# design.net
KiCad netlist of a schematic drawn in Altium Designer
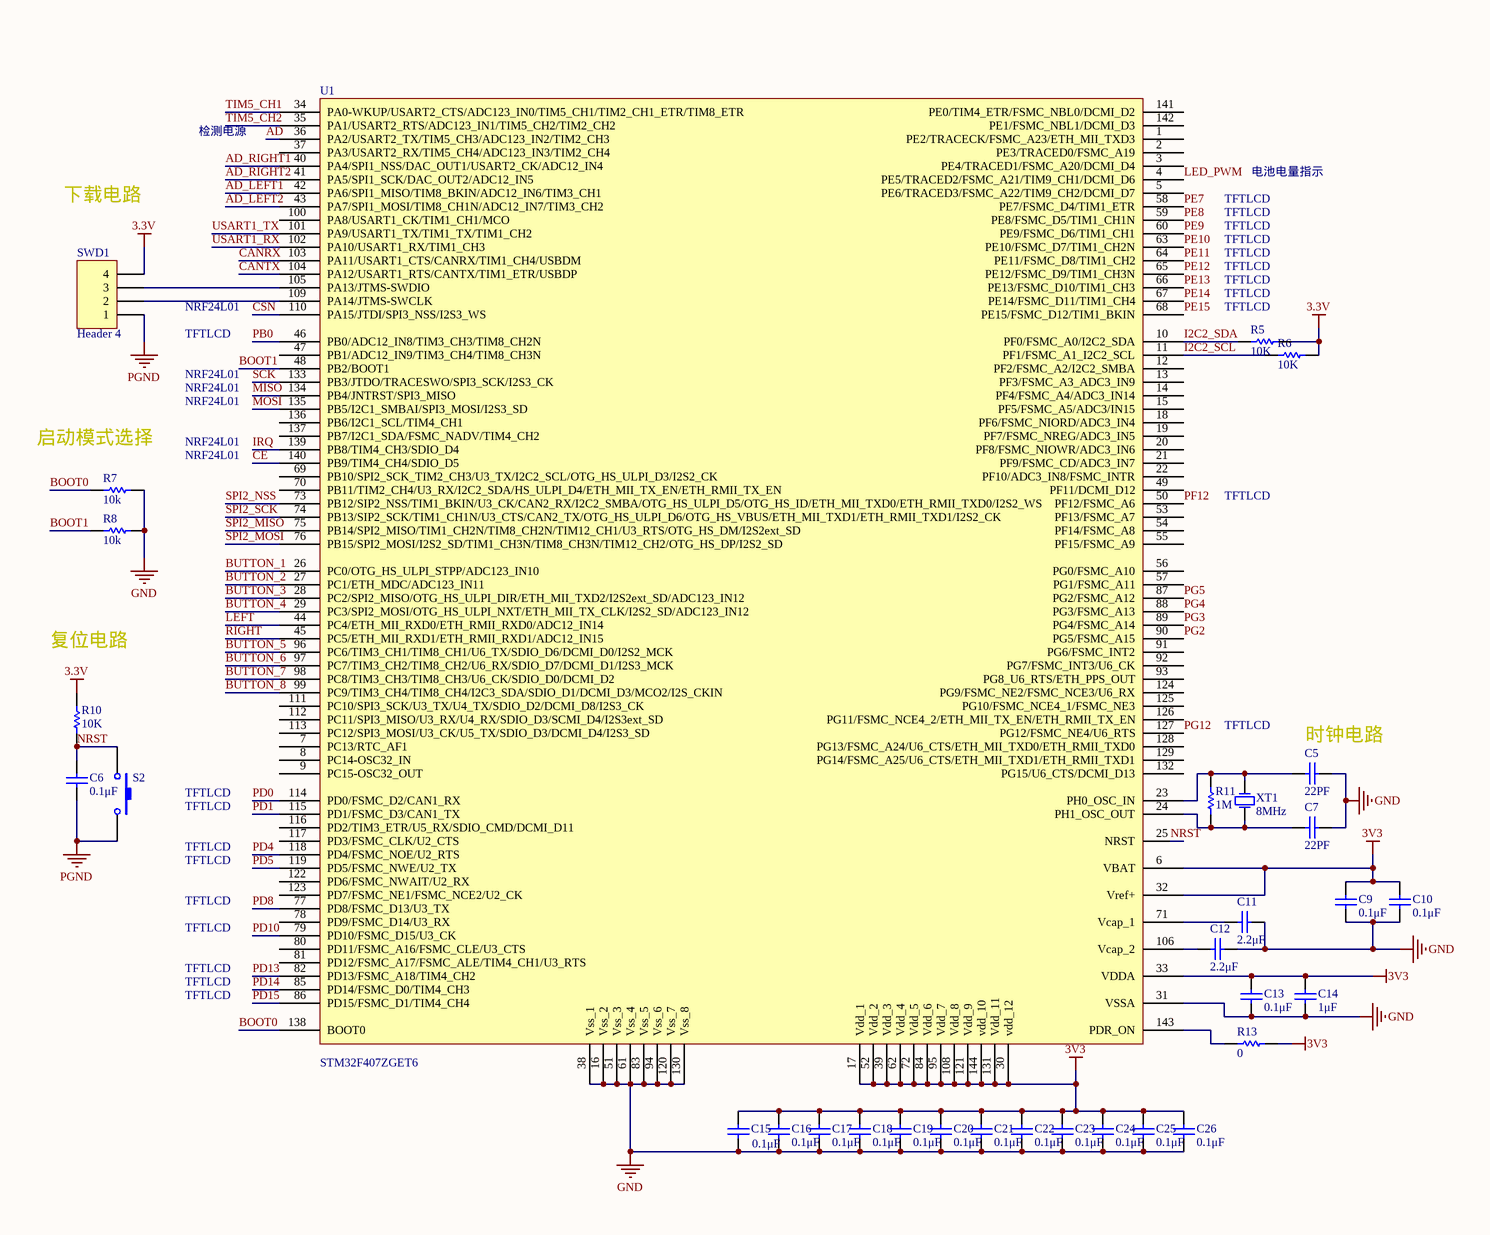
[diagram p0: 手柄.SchDoc, left]
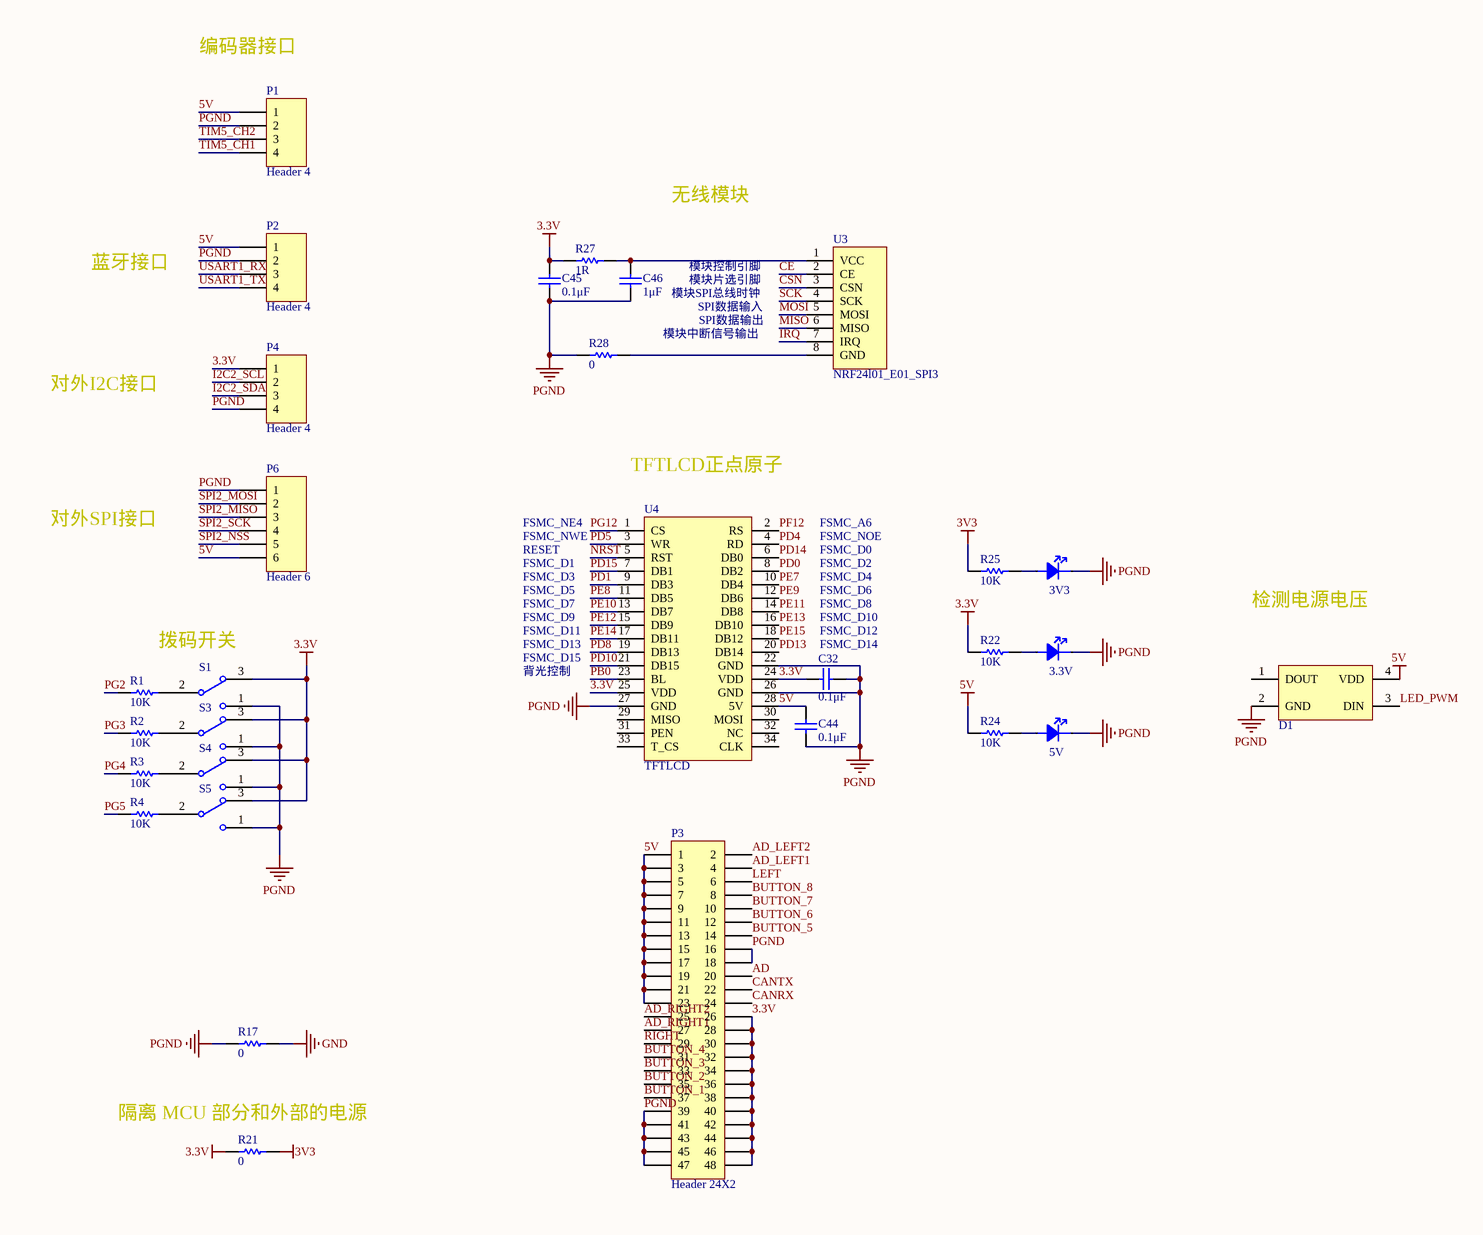
[diagram p1: 手柄.SchDoc, right]

(export (version "E")
  (design (tool "Eeschema 10.0.6"))
  (components
    (comp (ref "3.3V")
      (value "lED")
      (footprint "0805D")
      (description "LED")
      (libsource (lib "K60-mainboard-v3.1") (part "00-D-LED"))
    )
    (comp (ref "3V3")
      (value "lED")
      (footprint "0805D")
      (description "LED")
      (libsource (lib "K60-mainboard-v3.1") (part "00-D-LED"))
    )
    (comp (ref "5V")
      (value "lED")
      (footprint "0805D")
      (description "LED")
      (libsource (lib "K60-mainboard-v3.1") (part "00-D-LED"))
    )
    (comp (ref "C5")
      (value "22PF")
      (footprint "CAP-MLCC-0603")
      (description "无极性电容")
      (fields (field (name "PUBLISHER") "Altium Limited"))
      (libsource (lib "Libraries_2014_0618") (part "CAP"))
    )
    (comp (ref "C6")
      (value "0.1μF")
      (footprint "CAP-MLCC-0603")
      (description "无极性电容")
      (fields (field (name "PUBLISHER") "Altium Limited"))
      (libsource (lib "Libraries_2014_0618") (part "CAP"))
    )
    (comp (ref "C7")
      (value "22PF")
      (footprint "CAP-MLCC-0603")
      (description "无极性电容")
      (fields (field (name "PUBLISHER") "Altium Limited"))
      (libsource (lib "Libraries_2014_0618") (part "CAP"))
    )
    (comp (ref "C9")
      (value "0.1μF")
      (footprint "CAP-MLCC-0603")
      (description "无极性电容")
      (fields (field (name "PUBLISHER") "Altium Limited"))
      (libsource (lib "Libraries_2014_0618") (part "CAP"))
    )
    (comp (ref "C10")
      (value "0.1μF")
      (footprint "CAP-MLCC-0603")
      (description "无极性电容")
      (fields (field (name "PUBLISHER") "Altium Limited"))
      (libsource (lib "Libraries_2014_0618") (part "CAP"))
    )
    (comp (ref "C11")
      (value "2.2μF")
      (footprint "CAP-MLCC-0603")
      (description "无极性电容")
      (fields (field (name "PUBLISHER") "Altium Limited"))
      (libsource (lib "Libraries_2014_0618") (part "CAP"))
    )
    (comp (ref "C12")
      (value "2.2μF")
      (footprint "CAP-MLCC-0603")
      (description "无极性电容")
      (fields (field (name "PUBLISHER") "Altium Limited"))
      (libsource (lib "Libraries_2014_0618") (part "CAP"))
    )
    (comp (ref "C13")
      (value "0.1μF")
      (footprint "CAP-MLCC-0603")
      (description "无极性电容")
      (fields (field (name "PUBLISHER") "Altium Limited"))
      (libsource (lib "Libraries_2014_0618") (part "CAP"))
    )
    (comp (ref "C14")
      (value "1μF")
      (footprint "CAP-MLCC-0603")
      (description "无极性电容")
      (fields (field (name "PUBLISHER") "Altium Limited"))
      (libsource (lib "Libraries_2014_0618") (part "CAP"))
    )
    (comp (ref "C15")
      (value "0.1μF")
      (footprint "CAP-MLCC-0603")
      (description "无极性电容")
      (fields (field (name "PUBLISHER") "Altium Limited"))
      (libsource (lib "Libraries_2014_0618") (part "CAP"))
    )
    (comp (ref "C16")
      (value "0.1μF")
      (footprint "CAP-MLCC-0603")
      (description "无极性电容")
      (fields (field (name "PUBLISHER") "Altium Limited"))
      (libsource (lib "Libraries_2014_0618") (part "CAP"))
    )
    (comp (ref "C17")
      (value "0.1μF")
      (footprint "CAP-MLCC-0603")
      (description "无极性电容")
      (fields (field (name "PUBLISHER") "Altium Limited"))
      (libsource (lib "Libraries_2014_0618") (part "CAP"))
    )
    (comp (ref "C18")
      (value "0.1μF")
      (footprint "CAP-MLCC-0603")
      (description "无极性电容")
      (fields (field (name "PUBLISHER") "Altium Limited"))
      (libsource (lib "Libraries_2014_0618") (part "CAP"))
    )
    (comp (ref "C19")
      (value "0.1μF")
      (footprint "CAP-MLCC-0603")
      (description "无极性电容")
      (fields (field (name "PUBLISHER") "Altium Limited"))
      (libsource (lib "Libraries_2014_0618") (part "CAP"))
    )
    (comp (ref "C20")
      (value "0.1μF")
      (footprint "CAP-MLCC-0603")
      (description "无极性电容")
      (fields (field (name "PUBLISHER") "Altium Limited"))
      (libsource (lib "Libraries_2014_0618") (part "CAP"))
    )
    (comp (ref "C21")
      (value "0.1μF")
      (footprint "CAP-MLCC-0603")
      (description "无极性电容")
      (fields (field (name "PUBLISHER") "Altium Limited"))
      (libsource (lib "Libraries_2014_0618") (part "CAP"))
    )
    (comp (ref "C22")
      (value "0.1μF")
      (footprint "CAP-MLCC-0603")
      (description "无极性电容")
      (fields (field (name "PUBLISHER") "Altium Limited"))
      (libsource (lib "Libraries_2014_0618") (part "CAP"))
    )
    (comp (ref "C23")
      (value "0.1μF")
      (footprint "CAP-MLCC-0603")
      (description "无极性电容")
      (fields (field (name "PUBLISHER") "Altium Limited"))
      (libsource (lib "Libraries_2014_0618") (part "CAP"))
    )
    (comp (ref "C24")
      (value "0.1μF")
      (footprint "CAP-MLCC-0603")
      (description "无极性电容")
      (fields (field (name "PUBLISHER") "Altium Limited"))
      (libsource (lib "Libraries_2014_0618") (part "CAP"))
    )
    (comp (ref "C25")
      (value "0.1μF")
      (footprint "CAP-MLCC-0603")
      (description "无极性电容")
      (fields (field (name "PUBLISHER") "Altium Limited"))
      (libsource (lib "Libraries_2014_0618") (part "CAP"))
    )
    (comp (ref "C26")
      (value "0.1μF")
      (footprint "CAP-MLCC-0603")
      (description "无极性电容")
      (fields (field (name "PUBLISHER") "Altium Limited"))
      (libsource (lib "Libraries_2014_0618") (part "CAP"))
    )
    (comp (ref "C32")
      (value "0.1μF")
      (footprint "CAP-MLCC-0603")
      (description "无极性电容")
      (fields (field (name "PUBLISHER") "Altium Limited"))
      (libsource (lib "Libraries_2014_0618") (part "CAP"))
    )
    (comp (ref "C44")
      (value "0.1μF")
      (footprint "CAP-MLCC-0603")
      (description "无极性电容")
      (fields (field (name "PUBLISHER") "Altium Limited"))
      (libsource (lib "Libraries_2014_0618") (part "CAP"))
    )
    (comp (ref "C45")
      (value "0.1μF")
      (footprint "CAP-MLCC-0603")
      (description "无极性电容")
      (fields (field (name "PUBLISHER") "Altium Limited"))
      (libsource (lib "Libraries_2014_0618") (part "CAP"))
    )
    (comp (ref "C46")
      (value "1μF")
      (footprint "CAP-MLCC-0603")
      (description "无极性电容")
      (fields (field (name "PUBLISHER") "Altium Limited"))
      (libsource (lib "Libraries_2014_0618") (part "CAP"))
    )
    (comp (ref "D1")
      (value "LED_3535_SK6812")
      (footprint "PCB_ActiveLED:LED_3535_4P")
      (description "LED")
      (libsource (lib "SCH_Active") (part "LED_3535_SK6812"))
    )
    (comp (ref "P1")
      (value "Header 4")
      (footprint "HDR1X4")
      (description "Header, 4-Pin")
      (fields (field (name "PUBLISHER") "Altium Limited"))
      (libsource (lib "") (part "Header 4_1"))
    )
    (comp (ref "P2")
      (value "Header 4")
      (footprint "HDR1X4")
      (description "Header, 4-Pin")
      (fields (field (name "PUBLISHER") "Altium Limited"))
      (libsource (lib "") (part "Header 4_1"))
    )
    (comp (ref "P3")
      (value "Header 24X2")
      (footprint "手柄下板")
      (description "Header, 24-Pin, Dual row")
      (fields (field (name "PUBLISHER") "Altium Limited"))
      (libsource (lib "Libraries_2014_0618") (part "Header 24X2"))
    )
    (comp (ref "P4")
      (value "Header 4")
      (footprint "HDR1X4")
      (description "Header, 4-Pin")
      (fields (field (name "PUBLISHER") "Altium Limited"))
      (libsource (lib "Libraries_2014_0618") (part "Header 4"))
    )
    (comp (ref "P6")
      (value "Header 6")
      (footprint "Header 6")
      (description "Header, 6-Pin")
      (fields (field (name "PUBLISHER") "Altium Limited"))
      (libsource (lib "Libraries_2014_0618") (part "Header 6"))
    )
    (comp (ref "R1")
      (value "10K")
      (footprint "RES-0603")
      (description "Resistor")
      (fields (field (name "Comment") "Res1") (field (name "PUBLISHER") "Altium Limited"))
      (libsource (lib "K60-mainboard-v3.1") (part "Res1"))
    )
    (comp (ref "R2")
      (value "10K")
      (footprint "RES-0603")
      (description "Resistor")
      (fields (field (name "Comment") "Res1") (field (name "PUBLISHER") "Altium Limited"))
      (libsource (lib "K60-mainboard-v3.1") (part "Res1"))
    )
    (comp (ref "R3")
      (value "10K")
      (footprint "RES-0603")
      (description "Resistor")
      (fields (field (name "Comment") "Res1") (field (name "PUBLISHER") "Altium Limited"))
      (libsource (lib "K60-mainboard-v3.1") (part "Res1"))
    )
    (comp (ref "R4")
      (value "10K")
      (footprint "RES-0603")
      (description "Resistor")
      (fields (field (name "Comment") "Res1") (field (name "PUBLISHER") "Altium Limited"))
      (libsource (lib "K60-mainboard-v3.1") (part "Res1"))
    )
    (comp (ref "R5")
      (value "10K")
      (footprint "RES-0603")
      (description "Resistor")
      (fields (field (name "Comment") "Res1") (field (name "PUBLISHER") "Altium Limited"))
      (libsource (lib "K60-mainboard-v3.1") (part "Res1"))
    )
    (comp (ref "R6")
      (value "10K")
      (footprint "RES-0603")
      (description "Resistor")
      (fields (field (name "Comment") "Res1") (field (name "PUBLISHER") "Altium Limited"))
      (libsource (lib "K60-mainboard-v3.1") (part "Res1"))
    )
    (comp (ref "R7")
      (value "10k")
      (footprint "RES-0603")
      (description "Resistor")
      (fields (field (name "Comment") "Res1") (field (name "PUBLISHER") "Altium Limited"))
      (libsource (lib "K60-mainboard-v3.1") (part "Res1"))
    )
    (comp (ref "R8")
      (value "10k")
      (footprint "RES-0603")
      (description "Resistor")
      (fields (field (name "Comment") "Res1") (field (name "PUBLISHER") "Altium Limited"))
      (libsource (lib "K60-mainboard-v3.1") (part "Res1"))
    )
    (comp (ref "R10")
      (value "10K")
      (footprint "RES-0603")
      (description "Resistor")
      (fields (field (name "Comment") "Res1") (field (name "PUBLISHER") "Altium Limited"))
      (libsource (lib "K60-mainboard-v3.1") (part "Res1"))
    )
    (comp (ref "R11")
      (value "1M")
      (footprint "RES-0603")
      (description "Resistor")
      (fields (field (name "Comment") "Res1") (field (name "PUBLISHER") "Altium Limited"))
      (libsource (lib "K60-mainboard-v3.1") (part "Res1"))
    )
    (comp (ref "R13")
      (value "0")
      (footprint "RES-0603")
      (description "Resistor")
      (fields (field (name "Comment") "Res1") (field (name "PUBLISHER") "Altium Limited"))
      (libsource (lib "K60-mainboard-v3.1") (part "Res1"))
    )
    (comp (ref "R17")
      (value "0")
      (footprint "RES-0603")
      (description "Resistor")
      (fields (field (name "Comment") "Res1") (field (name "PUBLISHER") "Altium Limited"))
      (libsource (lib "K60-mainboard-v3.1") (part "Res1"))
    )
    (comp (ref "R21")
      (value "0")
      (footprint "RES-0603")
      (description "Resistor")
      (fields (field (name "Comment") "Res1") (field (name "PUBLISHER") "Altium Limited"))
      (libsource (lib "K60-mainboard-v3.1") (part "Res1"))
    )
    (comp (ref "R22")
      (value "10K")
      (footprint "RES-0603")
      (description "Resistor")
      (fields (field (name "Comment") "Res1") (field (name "PUBLISHER") "Altium Limited"))
      (libsource (lib "K60-mainboard-v3.1") (part "Res1"))
    )
    (comp (ref "R24")
      (value "10K")
      (footprint "RES-0603")
      (description "Resistor")
      (fields (field (name "Comment") "Res1") (field (name "PUBLISHER") "Altium Limited"))
      (libsource (lib "K60-mainboard-v3.1") (part "Res1"))
    )
    (comp (ref "R25")
      (value "10K")
      (footprint "RES-0603")
      (description "Resistor")
      (fields (field (name "Comment") "Res1") (field (name "PUBLISHER") "Altium Limited"))
      (libsource (lib "K60-mainboard-v3.1") (part "Res1"))
    )
    (comp (ref "R27")
      (value "1R")
      (footprint "RES-0603")
      (description "Resistor")
      (fields (field (name "Comment") "Res1") (field (name "PUBLISHER") "Altium Limited"))
      (libsource (lib "K60-mainboard-v3.1") (part "Res1"))
    )
    (comp (ref "R28")
      (value "0")
      (footprint "RES-0603")
      (description "Resistor")
      (fields (field (name "Comment") "Res1") (field (name "PUBLISHER") "Altium Limited"))
      (libsource (lib "K60-mainboard-v3.1") (part "Res1"))
    )
    (comp (ref "S1")
      (value "SW-SPDT")
      (footprint "拨码开关")
      (description "单刀双掷开关")
      (fields (field (name "PUBLISHER") "Altium Limited"))
      (libsource (lib "Libraries_2014_0618") (part "SW-SPDT"))
    )
    (comp (ref "S2")
      (value "SW-PB")
      (footprint "KEY")
      (description "按钮")
      (fields (field (name "PUBLISHER") "Altium Limited"))
      (libsource (lib "Libraries_2014_0618") (part "SW-PB"))
    )
    (comp (ref "S3")
      (value "SW-SPDT")
      (footprint "拨码开关")
      (description "单刀双掷开关")
      (fields (field (name "PUBLISHER") "Altium Limited"))
      (libsource (lib "Libraries_2014_0618") (part "SW-SPDT"))
    )
    (comp (ref "S4")
      (value "SW-SPDT")
      (footprint "拨码开关")
      (description "单刀双掷开关")
      (fields (field (name "PUBLISHER") "Altium Limited"))
      (libsource (lib "Libraries_2014_0618") (part "SW-SPDT"))
    )
    (comp (ref "S5")
      (value "SW-SPDT")
      (footprint "拨码开关")
      (description "单刀双掷开关")
      (fields (field (name "PUBLISHER") "Altium Limited"))
      (libsource (lib "Libraries_2014_0618") (part "SW-SPDT"))
    )
    (comp (ref "SWD1")
      (value "Header 4")
      (footprint "HDR1X4")
      (description "Header, 4-Pin")
      (fields (field (name "PUBLISHER") "Altium Limited"))
      (libsource (lib "K60-mainboard-v3.1") (part "Header 4"))
    )
    (comp (ref "U1")
      (value "STM32F407ZGET6")
      (footprint "LQFP144-L")
      (libsource (lib "STM32F407VGT6") (part "Component_1"))
    )
    (comp (ref "U3")
      (value "NRF24l01_E01_SPI3")
      (footprint "E01-ML01SP2")
      (libsource (lib "SCH_Module") (part "NRF24l01_E01_SPI2"))
    )
    (comp (ref "U4") (value "TFTLCD") (footprint "TFTLCD") (libsource (lib "sensor") (part "TFTLCD")))
    (comp (ref "XT1")
      (value "8MHz")
      (footprint "PCB_Oscillator:XT_5032_2")
      (description "Crystal Oscillator")
      (fields (field (name "Comment") "XTAL_5032_2P"))
      (libsource (lib "SCH_Oscillator") (part "XTAL_5032_2P"))
    )
  )
  (nets
    (net (code "1") (name "/AD") (class "Default")
      (node (ref "P3") (pin "20") (pinfunction "20_20") (pintype "passive"))
      (node (ref "U1") (pin "36") (pinfunction "PA2/USART2_TX/TIM5_CH3/ADC123_IN2/TIM2_CH3_36") (pintype "passive"))
    )
    (net (code "2") (name "/AD_LEFT1") (class "Default")
      (node (ref "P3") (pin "4") (pinfunction "4_4") (pintype "passive"))
      (node (ref "U1") (pin "42") (pinfunction "PA6/SPI1_MISO/TIM8_BKIN/ADC12_IN6/TIM3_CH1_42") (pintype "passive"))
    )
    (net (code "3") (name "/AD_LEFT2") (class "Default")
      (node (ref "P3") (pin "2") (pinfunction "2_2") (pintype "passive"))
      (node (ref "U1") (pin "43") (pinfunction "PA7/SPI1_MOSI/TIM8_CH1N/ADC12_IN7/TIM3_CH2_43") (pintype "passive"))
    )
    (net (code "4") (name "/AD_RIGHT1") (class "Default")
      (node (ref "P3") (pin "27") (pinfunction "27_27") (pintype "passive"))
      (node (ref "U1") (pin "40") (pinfunction "PA4/SPI1_NSS/DAC_OUT1/USART2_CK/ADC12_IN4_40") (pintype "passive"))
    )
    (net (code "5") (name "/AD_RIGHT2") (class "Default")
      (node (ref "P3") (pin "25") (pinfunction "25_25") (pintype "passive"))
      (node (ref "U1") (pin "41") (pinfunction "PA5/SPI1_SCK/DAC_OUT2/ADC12_IN5_41") (pintype "passive"))
    )
    (net (code "6") (name "/BOOT0") (class "Default")
      (node (ref "R7") (pin "1") (pinfunction "1_1") (pintype "passive"))
      (node (ref "U1") (pin "138") (pinfunction "BOOT0_138") (pintype "passive"))
    )
    (net (code "7") (name "/BOOT1") (class "Default")
      (node (ref "R8") (pin "1") (pinfunction "1_1") (pintype "passive"))
      (node (ref "U1") (pin "48") (pinfunction "PB2/BOOT1_48") (pintype "passive"))
    )
    (net (code "8") (name "/BUTTON_1") (class "Default")
      (node (ref "P3") (pin "37") (pinfunction "37_37") (pintype "passive"))
      (node (ref "U1") (pin "26") (pinfunction "PC0/OTG_HS_ULPI_STPP/ADC123_IN10_26") (pintype "passive"))
    )
    (net (code "9") (name "/BUTTON_2") (class "Default")
      (node (ref "P3") (pin "35") (pinfunction "35_35") (pintype "passive"))
      (node (ref "U1") (pin "27") (pinfunction "PC1/ETH_MDC/ADC123_IN11_27") (pintype "passive"))
    )
    (net (code "10") (name "/BUTTON_3") (class "Default")
      (node (ref "P3") (pin "33") (pinfunction "33_33") (pintype "passive"))
      (node (ref "U1") (pin "28") (pinfunction "PC2/SPI2_MISO/OTG_HS_ULPI_DIR/ETH_MII_TXD2/I2S2ext_SD/ADC123_IN12_28") (pintype "passive"))
    )
    (net (code "11") (name "/BUTTON_4") (class "Default")
      (node (ref "P3") (pin "31") (pinfunction "31_31") (pintype "passive"))
      (node (ref "U1") (pin "29") (pinfunction "PC3/SPI2_MOSI/OTG_HS_ULPI_NXT/ETH_MII_TX_CLK/I2S2_SD/ADC123_IN12_29") (pintype "passive"))
    )
    (net (code "12") (name "/BUTTON_5") (class "Default")
      (node (ref "P3") (pin "14") (pinfunction "14_14") (pintype "passive"))
      (node (ref "U1") (pin "96") (pinfunction "PC6/TIM3_CH1/TIM8_CH1/U6_TX/SDIO_D6/DCMI_D0/I2S2_MCK_96") (pintype "passive"))
    )
    (net (code "13") (name "/BUTTON_6") (class "Default")
      (node (ref "P3") (pin "12") (pinfunction "12_12") (pintype "passive"))
      (node (ref "U1") (pin "97") (pinfunction "PC7/TIM3_CH2/TIM8_CH2/U6_RX/SDIO_D7/DCMI_D1/I2S3_MCK_97") (pintype "passive"))
    )
    (net (code "14") (name "/BUTTON_7") (class "Default")
      (node (ref "P3") (pin "10") (pinfunction "10_10") (pintype "passive"))
      (node (ref "U1") (pin "98") (pinfunction "PC8/TIM3_CH3/TIM8_CH3/U6_CK/SDIO_D0/DCMI_D2_98") (pintype "passive"))
    )
    (net (code "15") (name "/BUTTON_8") (class "Default")
      (node (ref "P3") (pin "8") (pinfunction "8_8") (pintype "passive"))
      (node (ref "U1") (pin "99") (pinfunction "PC9/TIM3_CH4/TIM8_CH4/I2C3_SDA/SDIO_D1/DCMI_D3/MCO2/I2S_CKIN_99") (pintype "passive"))
    )
    (net (code "16") (name "/CANRX") (class "Default")
      (node (ref "P3") (pin "24") (pinfunction "24_24") (pintype "passive"))
      (node (ref "U1") (pin "103") (pinfunction "PA11/USART1_CTS/CANRX/TIM1_CH4/USBDM_103") (pintype "passive"))
    )
    (net (code "17") (name "/CANTX") (class "Default")
      (node (ref "P3") (pin "22") (pinfunction "22_22") (pintype "passive"))
      (node (ref "U1") (pin "104") (pinfunction "PA12/USART1_RTS/CANTX/TIM1_ETR/USBDP_104") (pintype "passive"))
    )
    (net (code "18") (name "/CE") (class "Default")
      (node (ref "U1") (pin "140") (pinfunction "PB9/TIM4_CH4/SDIO_D5_140") (pintype "passive"))
      (node (ref "U3") (pin "2") (pinfunction "CE_2") (pintype "passive"))
    )
    (net (code "19") (name "/CSN") (class "Default")
      (node (ref "U1") (pin "110") (pinfunction "PA15/JTDI/SPI3_NSS/I2S3_WS_110") (pintype "passive"))
      (node (ref "U3") (pin "3") (pinfunction "CSN_3") (pintype "passive"))
    )
    (net (code "20") (name "/I2C2_SCL") (class "Default")
      (node (ref "P4") (pin "2") (pinfunction "2_2") (pintype "passive"))
      (node (ref "R6") (pin "1") (pinfunction "1_1") (pintype "passive"))
      (node (ref "U1") (pin "11") (pinfunction "PF1/FSMC_A1_I2C2_SCL_11") (pintype "passive"))
    )
    (net (code "21") (name "/I2C2_SDA") (class "Default")
      (node (ref "P4") (pin "3") (pinfunction "3_3") (pintype "passive"))
      (node (ref "R5") (pin "1") (pinfunction "1_1") (pintype "passive"))
      (node (ref "U1") (pin "10") (pinfunction "PF0/FSMC_A0/I2C2_SDA_10") (pintype "passive"))
    )
    (net (code "22") (name "/IRQ") (class "Default")
      (node (ref "U1") (pin "139") (pinfunction "PB8/TIM4_CH3/SDIO_D4_139") (pintype "passive"))
      (node (ref "U3") (pin "7") (pinfunction "IRQ_7") (pintype "passive"))
    )
    (net (code "23") (name "/LED_PWM") (class "Default")
      (node (ref "D1") (pin "3") (pinfunction "DIN_3") (pintype "passive"))
      (node (ref "U1") (pin "4") (pinfunction "PE5/TRACED2/FSMC_A21/TIM9_CH1/DCMI_D6_4") (pintype "passive"))
    )
    (net (code "24") (name "/LEFT") (class "Default")
      (node (ref "P3") (pin "6") (pinfunction "6_6") (pintype "passive"))
      (node (ref "U1") (pin "44") (pinfunction "PC4/ETH_MII_RXD0/ETH_RMII_RXD0/ADC12_IN14_44") (pintype "passive"))
    )
    (net (code "25") (name "/MISO") (class "Default")
      (node (ref "U1") (pin "134") (pinfunction "PB4/JNTRST/SPI3_MISO_134") (pintype "passive"))
      (node (ref "U3") (pin "6") (pinfunction "MISO_6") (pintype "passive"))
    )
    (net (code "26") (name "/MOSI") (class "Default")
      (node (ref "U1") (pin "135") (pinfunction "PB5/I2C1_SMBAI/SPI3_MOSI/I2S3_SD_135") (pintype "passive"))
      (node (ref "U3") (pin "5") (pinfunction "MOSI_5") (pintype "passive"))
    )
    (net (code "27") (name "/NRST") (class "Default")
      (node (ref "C6") (pin "2") (pinfunction "2_2") (pintype "passive"))
      (node (ref "R10") (pin "2") (pinfunction "2_2") (pintype "passive"))
      (node (ref "S2") (pin "1") (pinfunction "1_1") (pintype "passive"))
      (node (ref "U1") (pin "25") (pinfunction "NRST_25") (pintype "passive"))
      (node (ref "U4") (pin "5") (pinfunction "RST_5") (pintype "passive"))
    )
    (net (code "28") (name "/PB0") (class "Default")
      (node (ref "U1") (pin "46") (pinfunction "PB0/ADC12_IN8/TIM3_CH3/TIM8_CH2N_46") (pintype "passive"))
      (node (ref "U4") (pin "23") (pinfunction "BL_23") (pintype "passive"))
    )
    (net (code "29") (name "/PD0") (class "Default")
      (node (ref "U1") (pin "114") (pinfunction "PD0/FSMC_D2/CAN1_RX_114") (pintype "passive"))
      (node (ref "U4") (pin "8") (pinfunction "DB2_8") (pintype "passive"))
    )
    (net (code "30") (name "/PD1") (class "Default")
      (node (ref "U1") (pin "115") (pinfunction "PD1/FSMC_D3/CAN1_TX_115") (pintype "passive"))
      (node (ref "U4") (pin "9") (pinfunction "DB3_9") (pintype "passive"))
    )
    (net (code "31") (name "/PD4") (class "Default")
      (node (ref "U1") (pin "118") (pinfunction "PD4/FSMC_NOE/U2_RTS_118") (pintype "passive"))
      (node (ref "U4") (pin "4") (pinfunction "RD_4") (pintype "passive"))
    )
    (net (code "32") (name "/PD5") (class "Default")
      (node (ref "U1") (pin "119") (pinfunction "PD5/FSMC_NWE/U2_TX_119") (pintype "passive"))
      (node (ref "U4") (pin "3") (pinfunction "WR_3") (pintype "passive"))
    )
    (net (code "33") (name "/PD8") (class "Default")
      (node (ref "U1") (pin "77") (pinfunction "PD8/FSMC_D13/U3_TX_77") (pintype "passive"))
      (node (ref "U4") (pin "19") (pinfunction "DB13_19") (pintype "passive"))
    )
    (net (code "34") (name "/PD10") (class "Default")
      (node (ref "U1") (pin "79") (pinfunction "PD10/FSMC_D15/U3_CK_79") (pintype "passive"))
      (node (ref "U4") (pin "21") (pinfunction "DB15_21") (pintype "passive"))
    )
    (net (code "35") (name "/PD13") (class "Default")
      (node (ref "U1") (pin "82") (pinfunction "PD13/FSMC_A18/TIM4_CH2_82") (pintype "passive"))
      (node (ref "U4") (pin "20") (pinfunction "DB14_20") (pintype "passive"))
    )
    (net (code "36") (name "/PD14") (class "Default")
      (node (ref "U1") (pin "85") (pinfunction "PD14/FSMC_D0/TIM4_CH3_85") (pintype "passive"))
      (node (ref "U4") (pin "6") (pinfunction "DB0_6") (pintype "passive"))
    )
    (net (code "37") (name "/PD15") (class "Default")
      (node (ref "U1") (pin "86") (pinfunction "PD15/FSMC_D1/TIM4_CH4_86") (pintype "passive"))
      (node (ref "U4") (pin "7") (pinfunction "DB1_7") (pintype "passive"))
    )
    (net (code "38") (name "/PE7") (class "Default")
      (node (ref "U1") (pin "58") (pinfunction "PE7/FSMC_D4/TIM1_ETR_58") (pintype "passive"))
      (node (ref "U4") (pin "10") (pinfunction "DB4_10") (pintype "passive"))
    )
    (net (code "39") (name "/PE8") (class "Default")
      (node (ref "U1") (pin "59") (pinfunction "PE8/FSMC_D5/TIM1_CH1N_59") (pintype "passive"))
      (node (ref "U4") (pin "11") (pinfunction "DB5_11") (pintype "passive"))
    )
    (net (code "40") (name "/PE9") (class "Default")
      (node (ref "U1") (pin "60") (pinfunction "PE9/FSMC_D6/TIM1_CH1_60") (pintype "passive"))
      (node (ref "U4") (pin "12") (pinfunction "DB6_12") (pintype "passive"))
    )
    (net (code "41") (name "/PE10") (class "Default")
      (node (ref "U1") (pin "63") (pinfunction "PE10/FSMC_D7/TIM1_CH2N_63") (pintype "passive"))
      (node (ref "U4") (pin "13") (pinfunction "DB7_13") (pintype "passive"))
    )
    (net (code "42") (name "/PE11") (class "Default")
      (node (ref "U1") (pin "64") (pinfunction "PE11/FSMC_D8/TIM1_CH2_64") (pintype "passive"))
      (node (ref "U4") (pin "14") (pinfunction "DB8_14") (pintype "passive"))
    )
    (net (code "43") (name "/PE12") (class "Default")
      (node (ref "U1") (pin "65") (pinfunction "PE12/FSMC_D9/TIM1_CH3N_65") (pintype "passive"))
      (node (ref "U4") (pin "15") (pinfunction "DB9_15") (pintype "passive"))
    )
    (net (code "44") (name "/PE13") (class "Default")
      (node (ref "U1") (pin "66") (pinfunction "PE13/FSMC_D10/TIM1_CH3_66") (pintype "passive"))
      (node (ref "U4") (pin "16") (pinfunction "DB10_16") (pintype "passive"))
    )
    (net (code "45") (name "/PE14") (class "Default")
      (node (ref "U1") (pin "67") (pinfunction "PE14/FSMC_D11/TIM1_CH4_67") (pintype "passive"))
      (node (ref "U4") (pin "17") (pinfunction "DB11_17") (pintype "passive"))
    )
    (net (code "46") (name "/PE15") (class "Default")
      (node (ref "U1") (pin "68") (pinfunction "PE15/FSMC_D12/TIM1_BKIN_68") (pintype "passive"))
      (node (ref "U4") (pin "18") (pinfunction "DB12_18") (pintype "passive"))
    )
    (net (code "47") (name "/PF12") (class "Default")
      (node (ref "U1") (pin "50") (pinfunction "PF12/FSMC_A6_50") (pintype "passive"))
      (node (ref "U4") (pin "2") (pinfunction "RS_2") (pintype "passive"))
    )
    (net (code "48") (name "/PG2") (class "Default")
      (node (ref "R1") (pin "1") (pinfunction "1_1") (pintype "passive"))
      (node (ref "U1") (pin "90") (pinfunction "PG5/FSMC_A15_90") (pintype "passive"))
    )
    (net (code "49") (name "/PG3") (class "Default")
      (node (ref "R2") (pin "1") (pinfunction "1_1") (pintype "passive"))
      (node (ref "U1") (pin "89") (pinfunction "PG4/FSMC_A14_89") (pintype "passive"))
    )
    (net (code "50") (name "/PG4") (class "Default")
      (node (ref "R3") (pin "1") (pinfunction "1_1") (pintype "passive"))
      (node (ref "U1") (pin "88") (pinfunction "PG3/FSMC_A13_88") (pintype "passive"))
    )
    (net (code "51") (name "/PG5") (class "Default")
      (node (ref "R4") (pin "1") (pinfunction "1_1") (pintype "passive"))
      (node (ref "U1") (pin "87") (pinfunction "PG2/FSMC_A12_87") (pintype "passive"))
    )
    (net (code "52") (name "/PG12") (class "Default")
      (node (ref "U1") (pin "127") (pinfunction "PG12/FSMC_NE4/U6_RTS_127") (pintype "passive"))
      (node (ref "U4") (pin "1") (pinfunction "CS_1") (pintype "passive"))
    )
    (net (code "53") (name "/RIGHT") (class "Default")
      (node (ref "P3") (pin "29") (pinfunction "29_29") (pintype "passive"))
      (node (ref "U1") (pin "45") (pinfunction "PC5/ETH_MII_RXD1/ETH_RMII_RXD1/ADC12_IN15_45") (pintype "passive"))
    )
    (net (code "54") (name "/SCK") (class "Default")
      (node (ref "U1") (pin "133") (pinfunction "PB3/JTDO/TRACESWO/SPI3_SCK/I2S3_CK_133") (pintype "passive"))
      (node (ref "U3") (pin "4") (pinfunction "SCK_4") (pintype "passive"))
    )
    (net (code "55") (name "/SPI2_MISO") (class "Default")
      (node (ref "P6") (pin "3") (pinfunction "3_3") (pintype "passive"))
      (node (ref "U1") (pin "75") (pinfunction "PB14/SPI2_MISO/TIM1_CH2N/TIM8_CH2N/TIM12_CH1/U3_RTS/OTG_HS_DM/I2S2ext_SD_75") (pintype "passive"))
    )
    (net (code "56") (name "/SPI2_MOSI") (class "Default")
      (node (ref "P6") (pin "2") (pinfunction "2_2") (pintype "passive"))
      (node (ref "U1") (pin "76") (pinfunction "PB15/SPI2_MOSI/I2S2_SD/TIM1_CH3N/TIM8_CH3N/TIM12_CH2/OTG_HS_DP/I2S2_SD_76") (pintype "passive"))
    )
    (net (code "57") (name "/SPI2_NSS") (class "Default")
      (node (ref "P6") (pin "5") (pinfunction "5_5") (pintype "passive"))
      (node (ref "U1") (pin "73") (pinfunction "PB12/SIP2_NSS/TIM1_BKIN/U3_CK/CAN2_RX/I2C2_SMBA/OTG_HS_ULPI_D5/OTG_HS_ID/ETH_MII_TXD0/ETH_RMII_TXD0/I2S2_WS_73") (pintype "passive"))
    )
    (net (code "58") (name "/SPI2_SCK") (class "Default")
      (node (ref "P6") (pin "4") (pinfunction "4_4") (pintype "passive"))
      (node (ref "U1") (pin "74") (pinfunction "PB13/SIP2_SCK/TIM1_CH1N/U3_CTS/CAN2_TX/OTG_HS_ULPI_D6/OTG_HS_VBUS/ETH_MII_TXD1/ETH_RMII_TXD1/I2S2_CK_74") (pintype "passive"))
    )
    (net (code "59") (name "/TIM5_CH1") (class "Default")
      (node (ref "P1") (pin "4") (pinfunction "4_4") (pintype "passive"))
      (node (ref "U1") (pin "34") (pinfunction "PA0-WKUP/USART2_CTS/ADC123_IN0/TIM5_CH1/TIM2_CH1_ETR/TIM8_ETR_34") (pintype "passive"))
    )
    (net (code "60") (name "/TIM5_CH2") (class "Default")
      (node (ref "P1") (pin "3") (pinfunction "3_3") (pintype "passive"))
      (node (ref "U1") (pin "35") (pinfunction "PA1/USART2_RTS/ADC123_IN1/TIM5_CH2/TIM2_CH2_35") (pintype "passive"))
    )
    (net (code "61") (name "/USART1_RX") (class "Default")
      (node (ref "P2") (pin "3") (pinfunction "3_3") (pintype "passive"))
      (node (ref "U1") (pin "102") (pinfunction "PA10/USART1_RX/TIM1_CH3_102") (pintype "passive"))
    )
    (net (code "62") (name "/USART1_TX") (class "Default")
      (node (ref "P2") (pin "4") (pinfunction "4_4") (pintype "passive"))
      (node (ref "U1") (pin "101") (pinfunction "PA9/USART1_TX/TIM1_TX/TIM1_CH2_101") (pintype "passive"))
    )
    (net (code "63") (name "3.3V") (class "Default")
      (node (ref "C32") (pin "1") (pinfunction "1_1") (pintype "passive"))
      (node (ref "C45") (pin "2") (pinfunction "2_2") (pintype "passive"))
      (node (ref "P3") (pin "26") (pinfunction "26_26") (pintype "passive"))
      (node (ref "P3") (pin "28") (pinfunction "28_28") (pintype "passive"))
      (node (ref "P3") (pin "30") (pinfunction "30_30") (pintype "passive"))
      (node (ref "P3") (pin "32") (pinfunction "32_32") (pintype "passive"))
      (node (ref "P3") (pin "34") (pinfunction "34_34") (pintype "passive"))
      (node (ref "P3") (pin "36") (pinfunction "36_36") (pintype "passive"))
      (node (ref "P3") (pin "38") (pinfunction "38_38") (pintype "passive"))
      (node (ref "P3") (pin "40") (pinfunction "40_40") (pintype "passive"))
      (node (ref "P3") (pin "42") (pinfunction "42_42") (pintype "passive"))
      (node (ref "P3") (pin "44") (pinfunction "44_44") (pintype "passive"))
      (node (ref "P3") (pin "46") (pinfunction "46_46") (pintype "passive"))
      (node (ref "P3") (pin "48") (pinfunction "48_48") (pintype "passive"))
      (node (ref "P4") (pin "1") (pinfunction "1_1") (pintype "passive"))
      (node (ref "R10") (pin "1") (pinfunction "1_1") (pintype "passive"))
      (node (ref "R21") (pin "1") (pinfunction "1_1") (pintype "passive"))
      (node (ref "R22") (pin "1") (pinfunction "1_1") (pintype "passive"))
      (node (ref "R27") (pin "1") (pinfunction "1_1") (pintype "passive"))
      (node (ref "R5") (pin "2") (pinfunction "2_2") (pintype "passive"))
      (node (ref "R6") (pin "2") (pinfunction "2_2") (pintype "passive"))
      (node (ref "S1") (pin "3") (pinfunction "3_3") (pintype "passive"))
      (node (ref "S3") (pin "3") (pinfunction "3_3") (pintype "passive"))
      (node (ref "S4") (pin "3") (pinfunction "3_3") (pintype "passive"))
      (node (ref "S5") (pin "3") (pinfunction "3_3") (pintype "passive"))
      (node (ref "SWD1") (pin "4") (pinfunction "4_4") (pintype "passive"))
      (node (ref "U4") (pin "24") (pinfunction "VDD_24") (pintype "passive"))
      (node (ref "U4") (pin "25") (pinfunction "VDD_25") (pintype "passive"))
    )
    (net (code "64") (name "3V3") (class "Default")
      (node (ref "C10") (pin "2") (pinfunction "2_2") (pintype "passive"))
      (node (ref "C13") (pin "2") (pinfunction "2_2") (pintype "passive"))
      (node (ref "C14") (pin "2") (pinfunction "2_2") (pintype "passive"))
      (node (ref "C15") (pin "2") (pinfunction "2_2") (pintype "passive"))
      (node (ref "C16") (pin "2") (pinfunction "2_2") (pintype "passive"))
      (node (ref "C17") (pin "2") (pinfunction "2_2") (pintype "passive"))
      (node (ref "C18") (pin "2") (pinfunction "2_2") (pintype "passive"))
      (node (ref "C19") (pin "2") (pinfunction "2_2") (pintype "passive"))
      (node (ref "C20") (pin "2") (pinfunction "2_2") (pintype "passive"))
      (node (ref "C21") (pin "2") (pinfunction "2_2") (pintype "passive"))
      (node (ref "C22") (pin "2") (pinfunction "2_2") (pintype "passive"))
      (node (ref "C23") (pin "2") (pinfunction "2_2") (pintype "passive"))
      (node (ref "C24") (pin "2") (pinfunction "2_2") (pintype "passive"))
      (node (ref "C25") (pin "2") (pinfunction "2_2") (pintype "passive"))
      (node (ref "C26") (pin "2") (pinfunction "2_2") (pintype "passive"))
      (node (ref "C9") (pin "2") (pinfunction "2_2") (pintype "passive"))
      (node (ref "R13") (pin "2") (pinfunction "2_2") (pintype "passive"))
      (node (ref "R21") (pin "2") (pinfunction "2_2") (pintype "passive"))
      (node (ref "R25") (pin "1") (pinfunction "1_1") (pintype "passive"))
      (node (ref "U1") (pin "108") (pinfunction "Vdd_8_108") (pintype "passive"))
      (node (ref "U1") (pin "121") (pinfunction "Vdd_9_121") (pintype "passive"))
      (node (ref "U1") (pin "131") (pinfunction "Vdd_11_131") (pintype "passive"))
      (node (ref "U1") (pin "144") (pinfunction "vdd_10_144") (pintype "passive"))
      (node (ref "U1") (pin "17") (pinfunction "Vdd_1_17") (pintype "passive"))
      (node (ref "U1") (pin "30") (pinfunction "vdd_12_30") (pintype "passive"))
      (node (ref "U1") (pin "32") (pinfunction "Vref+_32") (pintype "passive"))
      (node (ref "U1") (pin "33") (pinfunction "VDDA_33") (pintype "passive"))
      (node (ref "U1") (pin "39") (pinfunction "Vdd_3_39") (pintype "passive"))
      (node (ref "U1") (pin "52") (pinfunction "Vdd_2_52") (pintype "passive"))
      (node (ref "U1") (pin "6") (pinfunction "VBAT_6") (pintype "passive"))
      (node (ref "U1") (pin "62") (pinfunction "Vdd_4_62") (pintype "passive"))
      (node (ref "U1") (pin "72") (pinfunction "Vdd_5_72") (pintype "passive"))
      (node (ref "U1") (pin "84") (pinfunction "Vdd_6_84") (pintype "passive"))
      (node (ref "U1") (pin "95") (pinfunction "Vdd_7_95") (pintype "passive"))
    )
    (net (code "65") (name "5V") (class "Default")
      (node (ref "C44") (pin "1") (pinfunction "1_1") (pintype "passive"))
      (node (ref "D1") (pin "4") (pinfunction "VDD_4") (pintype "passive"))
      (node (ref "P1") (pin "1") (pinfunction "1_1") (pintype "passive"))
      (node (ref "P2") (pin "1") (pinfunction "1_1") (pintype "passive"))
      (node (ref "P3") (pin "1") (pinfunction "1_1") (pintype "passive"))
      (node (ref "P3") (pin "11") (pinfunction "11_11") (pintype "passive"))
      (node (ref "P3") (pin "13") (pinfunction "13_13") (pintype "passive"))
      (node (ref "P3") (pin "15") (pinfunction "15_15") (pintype "passive"))
      (node (ref "P3") (pin "17") (pinfunction "17_17") (pintype "passive"))
      (node (ref "P3") (pin "19") (pinfunction "19_19") (pintype "passive"))
      (node (ref "P3") (pin "21") (pinfunction "21_21") (pintype "passive"))
      (node (ref "P3") (pin "23") (pinfunction "23_23") (pintype "passive"))
      (node (ref "P3") (pin "3") (pinfunction "3_3") (pintype "passive"))
      (node (ref "P3") (pin "5") (pinfunction "5_5") (pintype "passive"))
      (node (ref "P3") (pin "7") (pinfunction "7_7") (pintype "passive"))
      (node (ref "P3") (pin "9") (pinfunction "9_9") (pintype "passive"))
      (node (ref "P6") (pin "6") (pinfunction "6_6") (pintype "passive"))
      (node (ref "R24") (pin "1") (pinfunction "1_1") (pintype "passive"))
      (node (ref "U4") (pin "28") (pinfunction "5V_28") (pintype "passive"))
    )
    (net (code "66") (name "GND") (class "Default")
      (node (ref "C10") (pin "1") (pinfunction "1_1") (pintype "passive"))
      (node (ref "C11") (pin "2") (pinfunction "2_2") (pintype "passive"))
      (node (ref "C12") (pin "2") (pinfunction "2_2") (pintype "passive"))
      (node (ref "C13") (pin "1") (pinfunction "1_1") (pintype "passive"))
      (node (ref "C14") (pin "1") (pinfunction "1_1") (pintype "passive"))
      (node (ref "C15") (pin "1") (pinfunction "1_1") (pintype "passive"))
      (node (ref "C16") (pin "1") (pinfunction "1_1") (pintype "passive"))
      (node (ref "C17") (pin "1") (pinfunction "1_1") (pintype "passive"))
      (node (ref "C18") (pin "1") (pinfunction "1_1") (pintype "passive"))
      (node (ref "C19") (pin "1") (pinfunction "1_1") (pintype "passive"))
      (node (ref "C20") (pin "1") (pinfunction "1_1") (pintype "passive"))
      (node (ref "C21") (pin "1") (pinfunction "1_1") (pintype "passive"))
      (node (ref "C22") (pin "1") (pinfunction "1_1") (pintype "passive"))
      (node (ref "C23") (pin "1") (pinfunction "1_1") (pintype "passive"))
      (node (ref "C24") (pin "1") (pinfunction "1_1") (pintype "passive"))
      (node (ref "C25") (pin "1") (pinfunction "1_1") (pintype "passive"))
      (node (ref "C26") (pin "1") (pinfunction "1_1") (pintype "passive"))
      (node (ref "C5") (pin "2") (pinfunction "2_2") (pintype "passive"))
      (node (ref "C7") (pin "2") (pinfunction "2_2") (pintype "passive"))
      (node (ref "C9") (pin "1") (pinfunction "1_1") (pintype "passive"))
      (node (ref "R17") (pin "2") (pinfunction "2_2") (pintype "passive"))
      (node (ref "R7") (pin "2") (pinfunction "2_2") (pintype "passive"))
      (node (ref "R8") (pin "2") (pinfunction "2_2") (pintype "passive"))
      (node (ref "U1") (pin "120") (pinfunction "Vss_7_120") (pintype "passive"))
      (node (ref "U1") (pin "130") (pinfunction "Vss_8_130") (pintype "passive"))
      (node (ref "U1") (pin "16") (pinfunction "Vss_2_16") (pintype "passive"))
      (node (ref "U1") (pin "31") (pinfunction "VSSA_31") (pintype "passive"))
      (node (ref "U1") (pin "38") (pinfunction "Vss_1_38") (pintype "passive"))
      (node (ref "U1") (pin "51") (pinfunction "Vss_3_51") (pintype "passive"))
      (node (ref "U1") (pin "61") (pinfunction "Vss_4_61") (pintype "passive"))
      (node (ref "U1") (pin "83") (pinfunction "Vss_5_83") (pintype "passive"))
      (node (ref "U1") (pin "94") (pinfunction "Vss_6_94") (pintype "passive"))
    )
    (net (code "67") (name "Net-(3.3V-1)") (class "Default")
      (node (ref "3.3V") (pin "A") (pinfunction "1_A") (pintype "passive"))
      (node (ref "R22") (pin "2") (pinfunction "2_2") (pintype "passive"))
    )
    (net (code "68") (name "Net-(3V3-1)") (class "Default")
      (node (ref "3V3") (pin "A") (pinfunction "1_A") (pintype "passive"))
      (node (ref "R25") (pin "2") (pinfunction "2_2") (pintype "passive"))
    )
    (net (code "69") (name "Net-(5V-1)") (class "Default")
      (node (ref "5V") (pin "A") (pinfunction "1_A") (pintype "passive"))
      (node (ref "R24") (pin "2") (pinfunction "2_2") (pintype "passive"))
    )
    (net (code "70") (name "Net-(R1-Pad2)") (class "Default")
      (node (ref "R1") (pin "2") (pinfunction "2_2") (pintype "passive"))
      (node (ref "S1") (pin "2") (pinfunction "2_2") (pintype "passive"))
    )
    (net (code "71") (name "Net-(R2-Pad2)") (class "Default")
      (node (ref "R2") (pin "2") (pinfunction "2_2") (pintype "passive"))
      (node (ref "S3") (pin "2") (pinfunction "2_2") (pintype "passive"))
    )
    (net (code "72") (name "Net-(R3-Pad2)") (class "Default")
      (node (ref "R3") (pin "2") (pinfunction "2_2") (pintype "passive"))
      (node (ref "S4") (pin "2") (pinfunction "2_2") (pintype "passive"))
    )
    (net (code "73") (name "Net-(R4-Pad2)") (class "Default")
      (node (ref "R4") (pin "2") (pinfunction "2_2") (pintype "passive"))
      (node (ref "S5") (pin "2") (pinfunction "2_2") (pintype "passive"))
    )
    (net (code "74") (name "Net-(U1-PA13{slash}JTMS-SWDIO)") (class "Default")
      (node (ref "SWD1") (pin "3") (pinfunction "3_3") (pintype "passive"))
      (node (ref "U1") (pin "105") (pinfunction "PA13/JTMS-SWDIO_105") (pintype "passive"))
    )
    (net (code "75") (name "Net-(U1-PA14{slash}JTMS-SWCLK)") (class "Default")
      (node (ref "SWD1") (pin "2") (pinfunction "2_2") (pintype "passive"))
      (node (ref "U1") (pin "109") (pinfunction "PA14/JTMS-SWCLK_109") (pintype "passive"))
    )
    (net (code "76") (name "Net-(U1-PDR_ON)") (class "Default")
      (node (ref "R13") (pin "1") (pinfunction "1_1") (pintype "passive"))
      (node (ref "U1") (pin "143") (pinfunction "PDR_ON_143") (pintype "passive"))
    )
    (net (code "77") (name "Net-(U1-PH0_OSC_IN)") (class "Default")
      (node (ref "C5") (pin "1") (pinfunction "1_1") (pintype "passive"))
      (node (ref "R11") (pin "2") (pinfunction "2_2") (pintype "passive"))
      (node (ref "U1") (pin "23") (pinfunction "PH0_OSC_IN_23") (pintype "passive"))
      (node (ref "XT1") (pin "1") (pinfunction "OSC1_1") (pintype "passive"))
    )
    (net (code "78") (name "Net-(U1-PH1_OSC_OUT)") (class "Default")
      (node (ref "C7") (pin "1") (pinfunction "1_1") (pintype "passive"))
      (node (ref "R11") (pin "1") (pinfunction "1_1") (pintype "passive"))
      (node (ref "U1") (pin "24") (pinfunction "PH1_OSC_OUT_24") (pintype "passive"))
      (node (ref "XT1") (pin "2") (pinfunction "OSC2_2") (pintype "passive"))
    )
    (net (code "79") (name "Net-(U1-Vcap_1)") (class "Default")
      (node (ref "C11") (pin "1") (pinfunction "1_1") (pintype "passive"))
      (node (ref "U1") (pin "71") (pinfunction "Vcap_1_71") (pintype "passive"))
    )
    (net (code "80") (name "Net-(U1-Vcap_2)") (class "Default")
      (node (ref "C12") (pin "1") (pinfunction "1_1") (pintype "passive"))
      (node (ref "U1") (pin "106") (pinfunction "Vcap_2_106") (pintype "passive"))
    )
    (net (code "81") (name "Net-(U3-GND)") (class "Default")
      (node (ref "R28") (pin "2") (pinfunction "2_2") (pintype "passive"))
      (node (ref "U3") (pin "8") (pinfunction "GND_8") (pintype "passive"))
    )
    (net (code "82") (name "Net-(U3-VCC)") (class "Default")
      (node (ref "C46") (pin "2") (pinfunction "2_2") (pintype "passive"))
      (node (ref "R27") (pin "2") (pinfunction "2_2") (pintype "passive"))
      (node (ref "U3") (pin "1") (pinfunction "VCC_1") (pintype "passive"))
    )
    (net (code "83") (name "PGND") (class "Default")
      (node (ref "3.3V") (pin "K") (pinfunction "2_K") (pintype "passive"))
      (node (ref "3V3") (pin "K") (pinfunction "2_K") (pintype "passive"))
      (node (ref "5V") (pin "K") (pinfunction "2_K") (pintype "passive"))
      (node (ref "C32") (pin "2") (pinfunction "2_2") (pintype "passive"))
      (node (ref "C44") (pin "2") (pinfunction "2_2") (pintype "passive"))
      (node (ref "C45") (pin "1") (pinfunction "1_1") (pintype "passive"))
      (node (ref "C46") (pin "1") (pinfunction "1_1") (pintype "passive"))
      (node (ref "C6") (pin "1") (pinfunction "1_1") (pintype "passive"))
      (node (ref "D1") (pin "2") (pinfunction "GND_2") (pintype "passive"))
      (node (ref "P1") (pin "2") (pinfunction "2_2") (pintype "passive"))
      (node (ref "P2") (pin "2") (pinfunction "2_2") (pintype "passive"))
      (node (ref "P3") (pin "16") (pinfunction "16_16") (pintype "passive"))
      (node (ref "P3") (pin "18") (pinfunction "18_18") (pintype "passive"))
      (node (ref "P3") (pin "39") (pinfunction "39_39") (pintype "passive"))
      (node (ref "P3") (pin "41") (pinfunction "41_41") (pintype "passive"))
      (node (ref "P3") (pin "43") (pinfunction "43_43") (pintype "passive"))
      (node (ref "P3") (pin "45") (pinfunction "45_45") (pintype "passive"))
      (node (ref "P3") (pin "47") (pinfunction "47_47") (pintype "passive"))
      (node (ref "P4") (pin "4") (pinfunction "4_4") (pintype "passive"))
      (node (ref "P6") (pin "1") (pinfunction "1_1") (pintype "passive"))
      (node (ref "R17") (pin "1") (pinfunction "1_1") (pintype "passive"))
      (node (ref "R28") (pin "1") (pinfunction "1_1") (pintype "passive"))
      (node (ref "S1") (pin "1") (pinfunction "1_1") (pintype "passive"))
      (node (ref "S2") (pin "2") (pinfunction "2_2") (pintype "passive"))
      (node (ref "S3") (pin "1") (pinfunction "1_1") (pintype "passive"))
      (node (ref "S4") (pin "1") (pinfunction "1_1") (pintype "passive"))
      (node (ref "S5") (pin "1") (pinfunction "1_1") (pintype "passive"))
      (node (ref "SWD1") (pin "1") (pinfunction "1_1") (pintype "passive"))
      (node (ref "U4") (pin "22") (pinfunction "GND_22") (pintype "passive"))
      (node (ref "U4") (pin "26") (pinfunction "GND_26") (pintype "passive"))
      (node (ref "U4") (pin "27") (pinfunction "GND_27") (pintype "passive"))
    )
    (net (code "84") (name "unconnected-(D1-DOUT-Pad1)") (class "Default")
      (node (ref "D1") (pin "1") (pinfunction "DOUT_1") (pintype "passive"))
    )
    (net (code "85") (name "unconnected-(U1-PA3{slash}USART2_RX{slash}TIM5_CH4{slash}ADC123_IN3{slash}TIM2_CH4-Pad37)") (class "Default")
      (node (ref "U1") (pin "37") (pinfunction "PA3/USART2_RX/TIM5_CH4/ADC123_IN3/TIM2_CH4_37") (pintype "passive"))
    )
    (net (code "86") (name "unconnected-(U1-PA8{slash}USART1_CK{slash}TIM1_CH1{slash}MCO-Pad100)") (class "Default")
      (node (ref "U1") (pin "100") (pinfunction "PA8/USART1_CK/TIM1_CH1/MCO_100") (pintype "passive"))
    )
    (net (code "87") (name "unconnected-(U1-PB1{slash}ADC12_IN9{slash}TIM3_CH4{slash}TIM8_CH3N-Pad47)") (class "Default")
      (node (ref "U1") (pin "47") (pinfunction "PB1/ADC12_IN9/TIM3_CH4/TIM8_CH3N_47") (pintype "passive"))
    )
    (net (code "88") (name "unconnected-(U1-PB6{slash}I2C1_SCL{slash}TIM4_CH1-Pad136)") (class "Default")
      (node (ref "U1") (pin "136") (pinfunction "PB6/I2C1_SCL/TIM4_CH1_136") (pintype "passive"))
    )
    (net (code "89") (name "unconnected-(U1-PB7{slash}I2C1_SDA{slash}FSMC_NADV{slash}TIM4_CH2-Pad137)") (class "Default")
      (node (ref "U1") (pin "137") (pinfunction "PB7/I2C1_SDA/FSMC_NADV/TIM4_CH2_137") (pintype "passive"))
    )
    (net (code "90") (name "unconnected-(U1-PB10{slash}SPI2_SCK_TIM2_CH3{slash}U3_TX{slash}I2C2_SCL{slash}OTG_HS_ULPI_D3{slash}I2S2_CK-Pad69)") (class "Default")
      (node (ref "U1") (pin "69") (pinfunction "PB10/SPI2_SCK_TIM2_CH3/U3_TX/I2C2_SCL/OTG_HS_ULPI_D3/I2S2_CK_69") (pintype "passive"))
    )
    (net (code "91") (name "unconnected-(U1-PB11{slash}TIM2_CH4{slash}U3_RX{slash}I2C2_SDA{slash}HS_ULPI_D4{slash}ETH_MII_TX_EN{slash}ETH_RMII_TX_EN-Pad70)") (class "Default")
      (node (ref "U1") (pin "70") (pinfunction "PB11/TIM2_CH4/U3_RX/I2C2_SDA/HS_ULPI_D4/ETH_MII_TX_EN/ETH_RMII_TX_EN_70") (pintype "passive"))
    )
    (net (code "92") (name "unconnected-(U1-PC10{slash}SPI3_SCK{slash}U3_TX{slash}U4_TX{slash}SDIO_D2{slash}DCMI_D8{slash}I2S3_CK-Pad111)") (class "Default")
      (node (ref "U1") (pin "111") (pinfunction "PC10/SPI3_SCK/U3_TX/U4_TX/SDIO_D2/DCMI_D8/I2S3_CK_111") (pintype "passive"))
    )
    (net (code "93") (name "unconnected-(U1-PC11{slash}SPI3_MISO{slash}U3_RX{slash}U4_RX{slash}SDIO_D3{slash}SCMI_D4{slash}I2S3ext_SD-Pad112)") (class "Default")
      (node (ref "U1") (pin "112") (pinfunction "PC11/SPI3_MISO/U3_RX/U4_RX/SDIO_D3/SCMI_D4/I2S3ext_SD_112") (pintype "passive"))
    )
    (net (code "94") (name "unconnected-(U1-PC12{slash}SPI3_MOSI{slash}U3_CK{slash}U5_TX{slash}SDIO_D3{slash}DCMI_D4{slash}I2S3_SD-Pad113)") (class "Default")
      (node (ref "U1") (pin "113") (pinfunction "PC12/SPI3_MOSI/U3_CK/U5_TX/SDIO_D3/DCMI_D4/I2S3_SD_113") (pintype "passive"))
    )
    (net (code "95") (name "unconnected-(U1-PC13{slash}RTC_AF1-Pad7)") (class "Default")
      (node (ref "U1") (pin "7") (pinfunction "PC13/RTC_AF1_7") (pintype "passive"))
    )
    (net (code "96") (name "unconnected-(U1-PC14-OSC32_IN-Pad8)") (class "Default")
      (node (ref "U1") (pin "8") (pinfunction "PC14-OSC32_IN_8") (pintype "passive"))
    )
    (net (code "97") (name "unconnected-(U1-PC15-OSC32_OUT-Pad9)") (class "Default")
      (node (ref "U1") (pin "9") (pinfunction "PC15-OSC32_OUT_9") (pintype "passive"))
    )
    (net (code "98") (name "unconnected-(U1-PD2{slash}TIM3_ETR{slash}U5_RX{slash}SDIO_CMD{slash}DCMI_D11-Pad116)") (class "Default")
      (node (ref "U1") (pin "116") (pinfunction "PD2/TIM3_ETR/U5_RX/SDIO_CMD/DCMI_D11_116") (pintype "passive"))
    )
    (net (code "99") (name "unconnected-(U1-PD3{slash}FSMC_CLK{slash}U2_CTS-Pad117)") (class "Default")
      (node (ref "U1") (pin "117") (pinfunction "PD3/FSMC_CLK/U2_CTS_117") (pintype "passive"))
    )
    (net (code "100") (name "unconnected-(U1-PD6{slash}FSMC_NWAIT{slash}U2_RX-Pad122)") (class "Default")
      (node (ref "U1") (pin "122") (pinfunction "PD6/FSMC_NWAIT/U2_RX_122") (pintype "passive"))
    )
    (net (code "101") (name "unconnected-(U1-PD7{slash}FSMC_NE1{slash}FSMC_NCE2{slash}U2_CK-Pad123)") (class "Default")
      (node (ref "U1") (pin "123") (pinfunction "PD7/FSMC_NE1/FSMC_NCE2/U2_CK_123") (pintype "passive"))
    )
    (net (code "102") (name "unconnected-(U1-PD9{slash}FSMC_D14{slash}U3_RX-Pad78)") (class "Default")
      (node (ref "U1") (pin "78") (pinfunction "PD9/FSMC_D14/U3_RX_78") (pintype "passive"))
    )
    (net (code "103") (name "unconnected-(U1-PD11{slash}FSMC_A16{slash}FSMC_CLE{slash}U3_CTS-Pad80)") (class "Default")
      (node (ref "U1") (pin "80") (pinfunction "PD11/FSMC_A16/FSMC_CLE/U3_CTS_80") (pintype "passive"))
    )
    (net (code "104") (name "unconnected-(U1-PD12{slash}FSMC_A17{slash}FSMC_ALE{slash}TIM4_CH1{slash}U3_RTS-Pad81)") (class "Default")
      (node (ref "U1") (pin "81") (pinfunction "PD12/FSMC_A17/FSMC_ALE/TIM4_CH1/U3_RTS_81") (pintype "passive"))
    )
    (net (code "105") (name "unconnected-(U1-PE0{slash}TIM4_ETR{slash}FSMC_NBL0{slash}DCMI_D2-Pad141)") (class "Default")
      (node (ref "U1") (pin "141") (pinfunction "PE0/TIM4_ETR/FSMC_NBL0/DCMI_D2_141") (pintype "passive"))
    )
    (net (code "106") (name "unconnected-(U1-PE1{slash}FSMC_NBL1{slash}DCMI_D3-Pad142)") (class "Default")
      (node (ref "U1") (pin "142") (pinfunction "PE1/FSMC_NBL1/DCMI_D3_142") (pintype "passive"))
    )
    (net (code "107") (name "unconnected-(U1-PE2{slash}TRACECK{slash}FSMC_A23{slash}ETH_MII_TXD3-Pad1)") (class "Default")
      (node (ref "U1") (pin "1") (pinfunction "PE2/TRACECK/FSMC_A23/ETH_MII_TXD3_1") (pintype "passive"))
    )
    (net (code "108") (name "unconnected-(U1-PE3{slash}TRACED0{slash}FSMC_A19-Pad2)") (class "Default")
      (node (ref "U1") (pin "2") (pinfunction "PE3/TRACED0/FSMC_A19_2") (pintype "passive"))
    )
    (net (code "109") (name "unconnected-(U1-PE4{slash}TRACED1{slash}FSMC_A20{slash}DCMI_D4-Pad3)") (class "Default")
      (node (ref "U1") (pin "3") (pinfunction "PE4/TRACED1/FSMC_A20/DCMI_D4_3") (pintype "passive"))
    )
    (net (code "110") (name "unconnected-(U1-PE6{slash}TRACED3{slash}FSMC_A22{slash}TIM9_CH2{slash}DCMI_D7-Pad5)") (class "Default")
      (node (ref "U1") (pin "5") (pinfunction "PE6/TRACED3/FSMC_A22/TIM9_CH2/DCMI_D7_5") (pintype "passive"))
    )
    (net (code "111") (name "unconnected-(U1-PF2{slash}FSMC_A2{slash}I2C2_SMBA-Pad12)") (class "Default")
      (node (ref "U1") (pin "12") (pinfunction "PF2/FSMC_A2/I2C2_SMBA_12") (pintype "passive"))
    )
    (net (code "112") (name "unconnected-(U1-PF3{slash}FSMC_A3_ADC3_IN9-Pad13)") (class "Default")
      (node (ref "U1") (pin "13") (pinfunction "PF3/FSMC_A3_ADC3_IN9_13") (pintype "passive"))
    )
    (net (code "113") (name "unconnected-(U1-PF4{slash}FSMC_A4{slash}ADC3_IN14-Pad14)") (class "Default")
      (node (ref "U1") (pin "14") (pinfunction "PF4/FSMC_A4/ADC3_IN14_14") (pintype "passive"))
    )
    (net (code "114") (name "unconnected-(U1-PF5{slash}FSMC_A5{slash}ADC3{slash}IN15-Pad15)") (class "Default")
      (node (ref "U1") (pin "15") (pinfunction "PF5/FSMC_A5/ADC3/IN15_15") (pintype "passive"))
    )
    (net (code "115") (name "unconnected-(U1-PF6{slash}FSMC_NIORD{slash}ADC3_IN4-Pad18)") (class "Default")
      (node (ref "U1") (pin "18") (pinfunction "PF6/FSMC_NIORD/ADC3_IN4_18") (pintype "passive"))
    )
    (net (code "116") (name "unconnected-(U1-PF7{slash}FSMC_NREG{slash}ADC3_IN5-Pad19)") (class "Default")
      (node (ref "U1") (pin "19") (pinfunction "PF7/FSMC_NREG/ADC3_IN5_19") (pintype "passive"))
    )
    (net (code "117") (name "unconnected-(U1-PF8{slash}FSMC_NIOWR{slash}ADC3_IN6-Pad20)") (class "Default")
      (node (ref "U1") (pin "20") (pinfunction "PF8/FSMC_NIOWR/ADC3_IN6_20") (pintype "passive"))
    )
    (net (code "118") (name "unconnected-(U1-PF9{slash}FSMC_CD{slash}ADC3_IN7-Pad21)") (class "Default")
      (node (ref "U1") (pin "21") (pinfunction "PF9/FSMC_CD/ADC3_IN7_21") (pintype "passive"))
    )
    (net (code "119") (name "unconnected-(U1-PF10{slash}ADC3_IN8{slash}FSMC_INTR-Pad22)") (class "Default")
      (node (ref "U1") (pin "22") (pinfunction "PF10/ADC3_IN8/FSMC_INTR_22") (pintype "passive"))
    )
    (net (code "120") (name "unconnected-(U1-PF11{slash}DCMI_D12-Pad49)") (class "Default")
      (node (ref "U1") (pin "49") (pinfunction "PF11/DCMI_D12_49") (pintype "passive"))
    )
    (net (code "121") (name "unconnected-(U1-PF13{slash}FSMC_A7-Pad53)") (class "Default")
      (node (ref "U1") (pin "53") (pinfunction "PF13/FSMC_A7_53") (pintype "passive"))
    )
    (net (code "122") (name "unconnected-(U1-PF14{slash}FSMC_A8-Pad54)") (class "Default")
      (node (ref "U1") (pin "54") (pinfunction "PF14/FSMC_A8_54") (pintype "passive"))
    )
    (net (code "123") (name "unconnected-(U1-PF15{slash}FSMC_A9-Pad55)") (class "Default")
      (node (ref "U1") (pin "55") (pinfunction "PF15/FSMC_A9_55") (pintype "passive"))
    )
    (net (code "124") (name "unconnected-(U1-PG0{slash}FSMC_A10-Pad56)") (class "Default")
      (node (ref "U1") (pin "56") (pinfunction "PG0/FSMC_A10_56") (pintype "passive"))
    )
    (net (code "125") (name "unconnected-(U1-PG1{slash}FSMC_A11-Pad57)") (class "Default")
      (node (ref "U1") (pin "57") (pinfunction "PG1/FSMC_A11_57") (pintype "passive"))
    )
    (net (code "126") (name "unconnected-(U1-PG6{slash}FSMC_INT2-Pad91)") (class "Default")
      (node (ref "U1") (pin "91") (pinfunction "PG6/FSMC_INT2_91") (pintype "passive"))
    )
    (net (code "127") (name "unconnected-(U1-PG7{slash}FSMC_INT3{slash}U6_CK-Pad92)") (class "Default")
      (node (ref "U1") (pin "92") (pinfunction "PG7/FSMC_INT3/U6_CK_92") (pintype "passive"))
    )
    (net (code "128") (name "unconnected-(U1-PG8_U6_RTS{slash}ETH_PPS_OUT-Pad93)") (class "Default")
      (node (ref "U1") (pin "93") (pinfunction "PG8_U6_RTS/ETH_PPS_OUT_93") (pintype "passive"))
    )
    (net (code "129") (name "unconnected-(U1-PG9{slash}FSMC_NE2{slash}FSMC_NCE3{slash}U6_RX-Pad124)") (class "Default")
      (node (ref "U1") (pin "124") (pinfunction "PG9/FSMC_NE2/FSMC_NCE3/U6_RX_124") (pintype "passive"))
    )
    (net (code "130") (name "unconnected-(U1-PG10{slash}FSMC_NCE4_1{slash}FSMC_NE3-Pad125)") (class "Default")
      (node (ref "U1") (pin "125") (pinfunction "PG10/FSMC_NCE4_1/FSMC_NE3_125") (pintype "passive"))
    )
    (net (code "131") (name "unconnected-(U1-PG11{slash}FSMC_NCE4_2{slash}ETH_MII_TX_EN{slash}ETH_RMII_TX_EN-Pad126)") (class "Default")
      (node (ref "U1") (pin "126") (pinfunction "PG11/FSMC_NCE4_2/ETH_MII_TX_EN/ETH_RMII_TX_EN_126") (pintype "passive"))
    )
    (net (code "132") (name "unconnected-(U1-PG13{slash}FSMC_A24{slash}U6_CTS{slash}ETH_MII_TXD0{slash}ETH_RMII_TXD0-Pad128)") (class "Default")
      (node (ref "U1") (pin "128") (pinfunction "PG13/FSMC_A24/U6_CTS/ETH_MII_TXD0/ETH_RMII_TXD0_128") (pintype "passive"))
    )
    (net (code "133") (name "unconnected-(U1-PG14{slash}FSMC_A25{slash}U6_CTS{slash}ETH_MII_TXD1{slash}ETH_RMII_TXD1-Pad129)") (class "Default")
      (node (ref "U1") (pin "129") (pinfunction "PG14/FSMC_A25/U6_CTS/ETH_MII_TXD1/ETH_RMII_TXD1_129") (pintype "passive"))
    )
    (net (code "134") (name "unconnected-(U1-PG15{slash}U6_CTS{slash}DCMI_D13-Pad132)") (class "Default")
      (node (ref "U1") (pin "132") (pinfunction "PG15/U6_CTS/DCMI_D13_132") (pintype "passive"))
    )
    (net (code "135") (name "unconnected-(U4-CLK-Pad34)") (class "Default")
      (node (ref "U4") (pin "34") (pinfunction "CLK_34") (pintype "passive"))
    )
    (net (code "136") (name "unconnected-(U4-MISO-Pad29)") (class "Default")
      (node (ref "U4") (pin "29") (pinfunction "MISO_29") (pintype "passive"))
    )
    (net (code "137") (name "unconnected-(U4-MOSI-Pad30)") (class "Default")
      (node (ref "U4") (pin "30") (pinfunction "MOSI_30") (pintype "passive"))
    )
    (net (code "138") (name "unconnected-(U4-NC-Pad32)") (class "Default")
      (node (ref "U4") (pin "32") (pinfunction "NC_32") (pintype "passive"))
    )
    (net (code "139") (name "unconnected-(U4-PEN-Pad31)") (class "Default")
      (node (ref "U4") (pin "31") (pinfunction "PEN_31") (pintype "passive"))
    )
    (net (code "140") (name "unconnected-(U4-T_CS-Pad33)") (class "Default")
      (node (ref "U4") (pin "33") (pinfunction "T_CS_33") (pintype "passive"))
    )
  )
)
